# design.net
KiCad netlist of a schematic drawn in Altium Designer
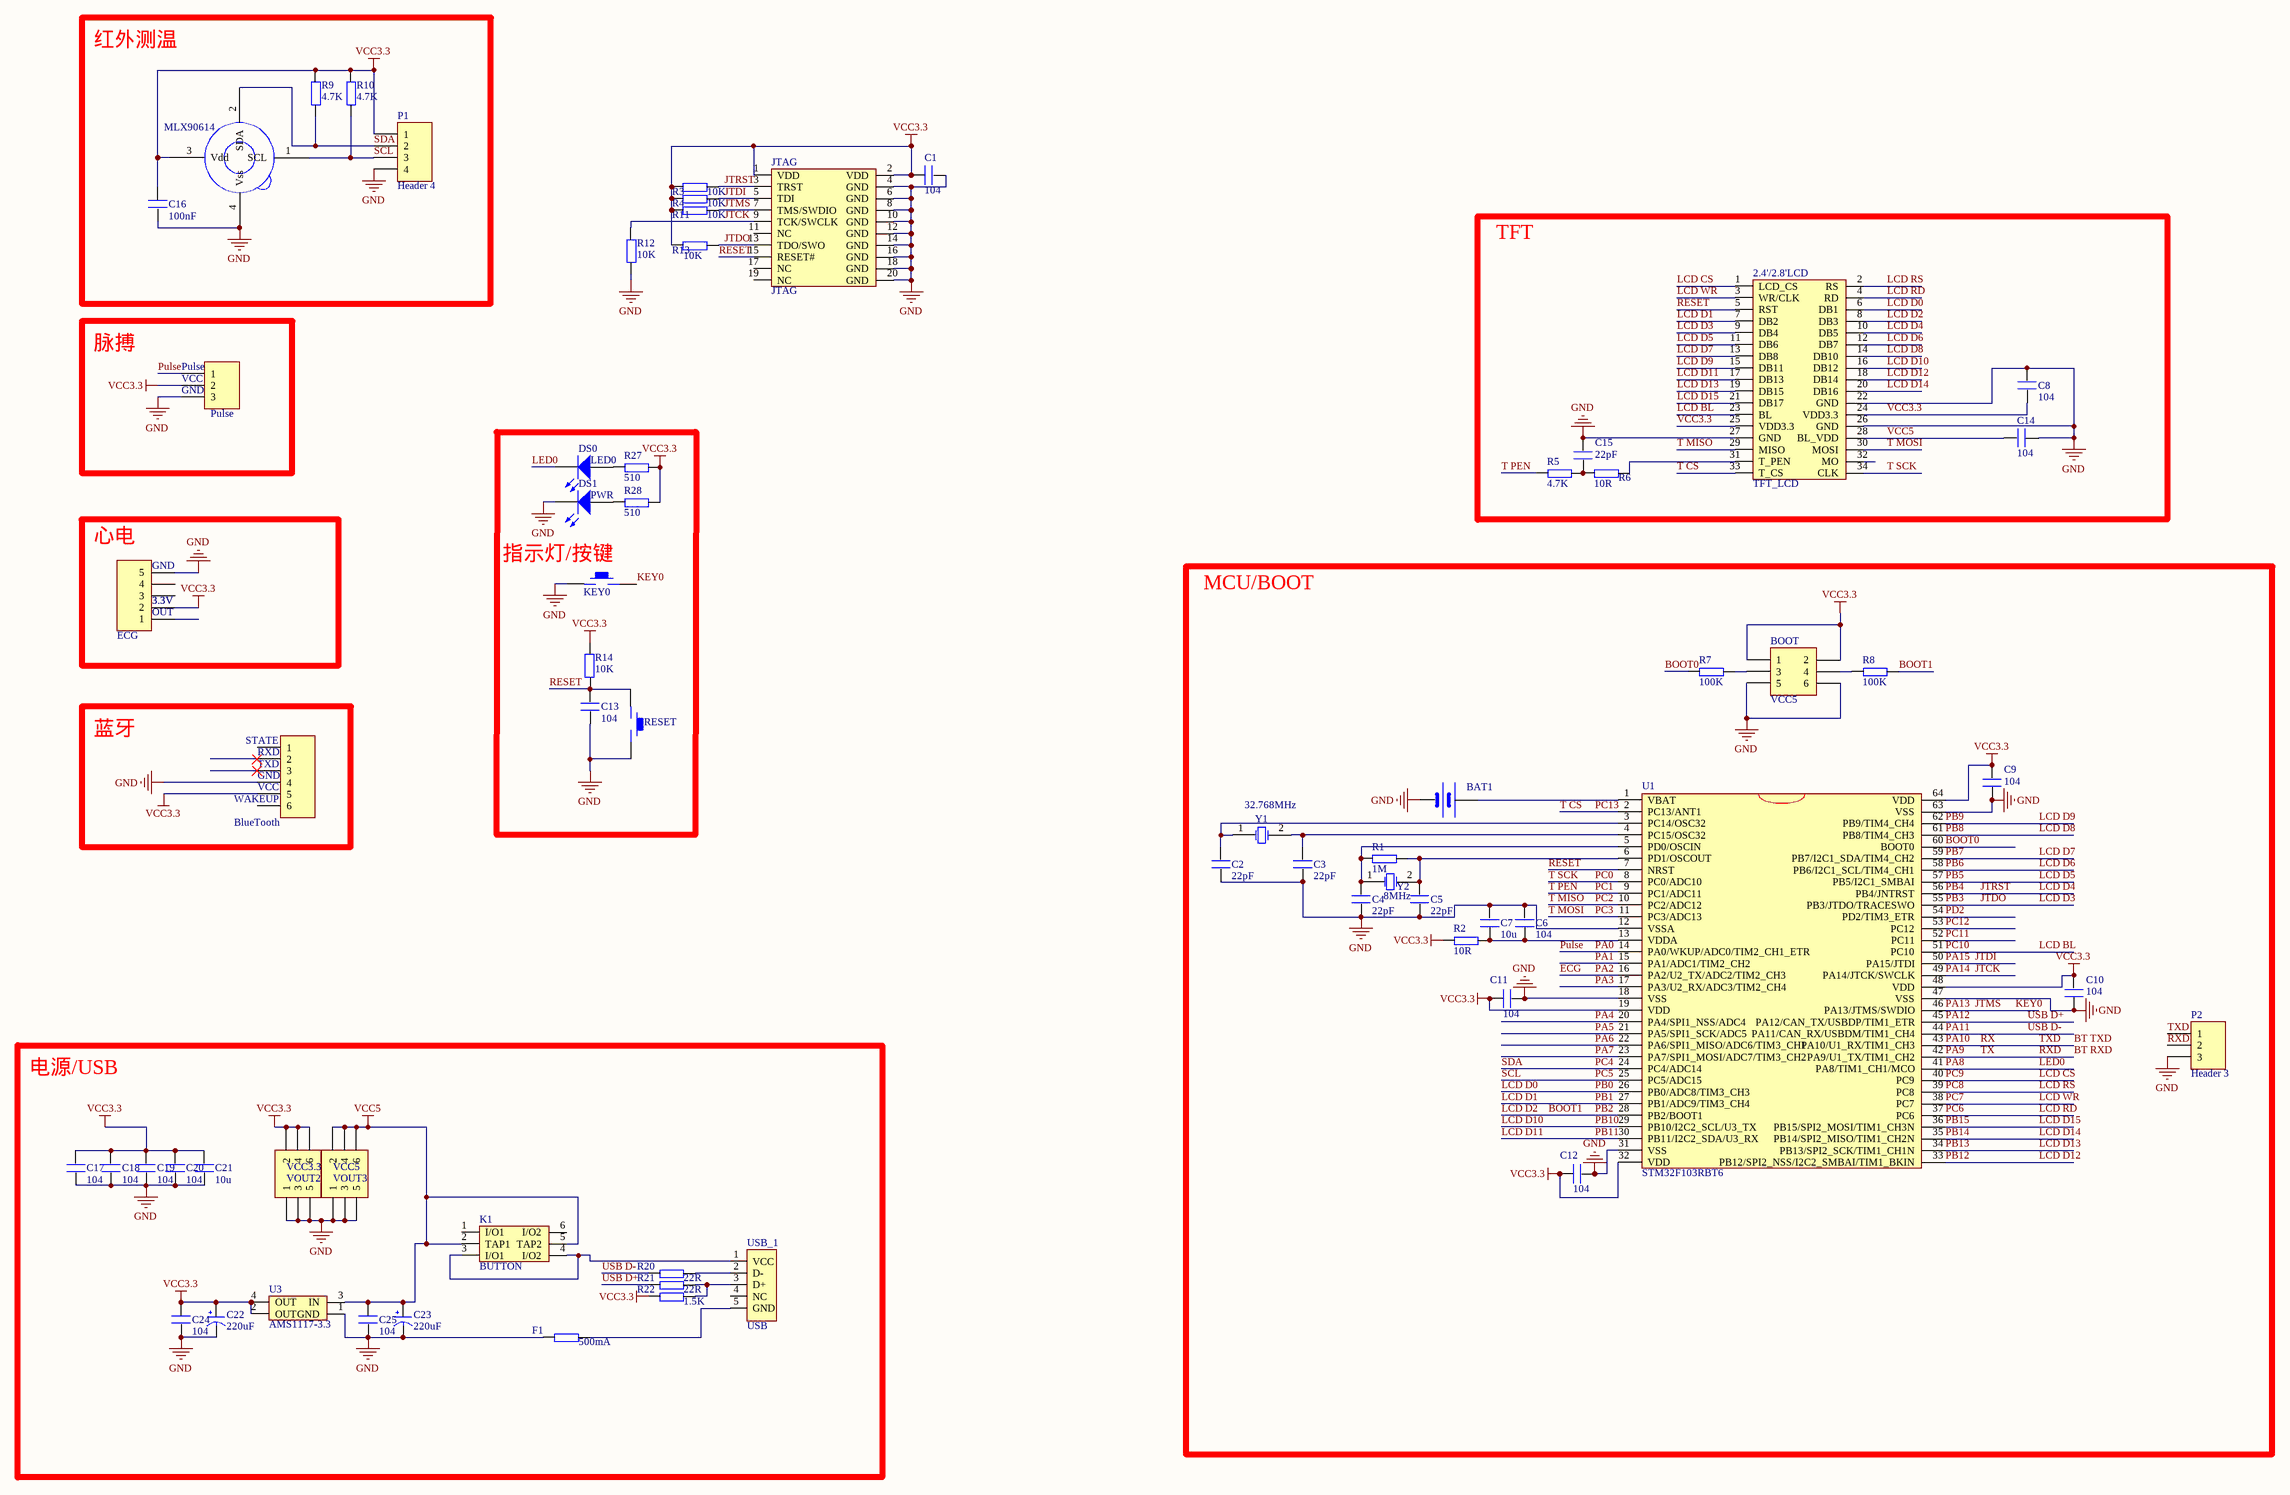
[diagram p0: 远程医疗.SchDoc]

(export (version "E")
  (design (tool "Eeschema 10.0.6"))
  (components
    (comp (ref "2.4'/2.8'LCD")
      (value "TFT_LCD")
      (footprint "DB2*17")
      (libsource (lib "MiniSTM32 V2.0封装库") (part "TFT_LCD"))
    )
    (comp (ref "BAT1") (value "BATT") (footprint "BATM") (libsource (lib "MiniSTM32 V2.0封装库") (part "BAT")))
    (comp (ref "BlueTooth")
      (value "BlueTooth")
      (footprint "BlueTooth")
      (libsource (lib "my Integrated lib ") (part "BlueTooth"))
    )
    (comp (ref "BOOT")
      (value "VCC5")
      (footprint "HDR2X3")
      (description "Header, 3-Pin, Dual row")
      (fields (field (name "PUBLISHER") "Altium Limited"))
      (libsource (lib "MiniSTM32 V2.0封装库") (part "Header 3X2"))
    )
    (comp (ref "C1") (value "104") (footprint "0603P") (libsource (lib "MiniSTM32 V2.0封装库") (part "C")))
    (comp (ref "C2") (value "22pF") (footprint "0603P") (libsource (lib "MiniSTM32 V2.0封装库") (part "C")))
    (comp (ref "C3") (value "22pF") (footprint "0603P") (libsource (lib "MiniSTM32 V2.0封装库") (part "C")))
    (comp (ref "C4") (value "22pF") (footprint "0603P") (libsource (lib "MiniSTM32 V2.0封装库") (part "C")))
    (comp (ref "C5") (value "22pF") (footprint "0603P") (libsource (lib "MiniSTM32 V2.0封装库") (part "C")))
    (comp (ref "C6") (value "104") (footprint "0603P") (libsource (lib "MiniSTM32 V2.0封装库") (part "C")))
    (comp (ref "C7") (value "10u") (footprint "0603P") (libsource (lib "MiniSTM32 V2.0封装库") (part "C")))
    (comp (ref "C8") (value "104") (footprint "0603P") (libsource (lib "MiniSTM32 V2.0封装库") (part "C")))
    (comp (ref "C9") (value "104") (footprint "0603P") (libsource (lib "MiniSTM32 V2.0封装库") (part "C")))
    (comp (ref "C10") (value "104") (footprint "0603P") (libsource (lib "MiniSTM32 V2.0封装库") (part "C")))
    (comp (ref "C11") (value "104") (footprint "0603P") (libsource (lib "MiniSTM32 V2.0封装库") (part "C")))
    (comp (ref "C12") (value "104") (footprint "0603P") (libsource (lib "MiniSTM32 V2.0封装库") (part "C")))
    (comp (ref "C13") (value "104") (footprint "0603P") (libsource (lib "MiniSTM32 V2.0封装库") (part "C")))
    (comp (ref "C14") (value "104") (footprint "0603P") (libsource (lib "MiniSTM32 V2.0封装库") (part "C")))
    (comp (ref "C15") (value "22pF") (footprint "0603P") (libsource (lib "MiniSTM32 V2.0封装库") (part "C")))
    (comp (ref "C16") (value "100nF") (footprint "0603P") (libsource (lib "MiniSTM32 V2.0封装库") (part "C")))
    (comp (ref "C17") (value "104") (footprint "0603P") (libsource (lib "MiniSTM32 V2.0封装库") (part "C")))
    (comp (ref "C18") (value "104") (footprint "0603P") (libsource (lib "MiniSTM32 V2.0封装库") (part "C")))
    (comp (ref "C19") (value "104") (footprint "0603P") (libsource (lib "MiniSTM32 V2.0封装库") (part "C")))
    (comp (ref "C20") (value "104") (footprint "0603P") (libsource (lib "MiniSTM32 V2.0封装库") (part "C")))
    (comp (ref "C21") (value "10u") (footprint "0603P") (libsource (lib "MiniSTM32 V2.0封装库") (part "C")))
    (comp (ref "C22")
      (value "220uF")
      (footprint "CC6.56.5")
      (libsource (lib "MiniSTM32 V2.0封装库") (part "CAP"))
    )
    (comp (ref "C23")
      (value "220uF")
      (footprint "CC6.56.5")
      (libsource (lib "MiniSTM32 V2.0封装库") (part "CAP"))
    )
    (comp (ref "C24") (value "104") (footprint "0603P") (libsource (lib "MiniSTM32 V2.0封装库") (part "C")))
    (comp (ref "C25") (value "104") (footprint "0603P") (libsource (lib "MiniSTM32 V2.0封装库") (part "C")))
    (comp (ref "DS0")
      (value "LED0")
      (footprint "SMDLED")
      (description "Typical RED, GREEN, YELLOW, AMBER GaAs LED")
      (fields (field (name "PUBLISHER") "Altium Limited"))
      (libsource (lib "MiniSTM32 V2.0封装库") (part "LED2"))
    )
    (comp (ref "DS1")
      (value "PWR")
      (footprint "SMDLED")
      (description "Typical RED, GREEN, YELLOW, AMBER GaAs LED")
      (fields (field (name "PUBLISHER") "Altium Limited"))
      (libsource (lib "MiniSTM32 V2.0封装库") (part "LED2"))
    )
    (comp (ref "ECG") (value "ECG") (footprint "ECG") (libsource (lib "my Integrated lib ") (part "ECG")))
    (comp (ref "F1") (value "500mA") (footprint "0603P") (libsource (lib "MiniSTM32 V2.0封装库") (part "R")))
    (comp (ref "JTAG") (value "JTAG") (footprint "JTAG_20") (libsource (lib "CORE") (part "JTAG")))
    (comp (ref "K1")
      (value "BUTTON")
      (footprint "BTN8.5*8.5")
      (libsource (lib "MiniSTM32 V2.0封装库") (part "BUTTON"))
    )
    (comp (ref "KEY0") (value "KEY_M") (footprint "KEY_M") (libsource (lib "") (part "KEY_M_1")))
    (comp (ref "MLX90614")
      (value "MLX90614")
      (footprint "MLX90614")
      (libsource (lib "my Integrated lib ") (part "MLX90614"))
    )
    (comp (ref "P1")
      (value "Header 4")
      (footprint "HDR1X4")
      (description "Header, 4-Pin")
      (fields (field (name "PUBLISHER") "Altium Limited"))
      (libsource (lib "Miscellaneous Connectors") (part "Header 4"))
    )
    (comp (ref "P2")
      (value "Header 3")
      (footprint "HDR1X3")
      (description "Header, 3-Pin")
      (fields (field (name "PUBLISHER") "Altium Limited"))
      (libsource (lib "Miscellaneous Connectors") (part "Header 3"))
    )
    (comp (ref "Pulse")
      (value "Pulse")
      (footprint "Pulse")
      (libsource (lib "my Integrated lib ") (part "Pulse"))
    )
    (comp (ref "R1") (value "1M") (footprint "0603P") (libsource (lib "MiniSTM32 V2.0封装库") (part "R")))
    (comp (ref "R2") (value "10R") (footprint "0603P") (libsource (lib "MiniSTM32 V2.0封装库") (part "R")))
    (comp (ref "R3") (value "10K") (footprint "0603P") (libsource (lib "MiniSTM32 V2.0封装库") (part "R")))
    (comp (ref "R4") (value "10K") (footprint "0603P") (libsource (lib "MiniSTM32 V2.0封装库") (part "R")))
    (comp (ref "R5") (value "4.7K") (footprint "0603P") (libsource (lib "MiniSTM32 V2.0封装库") (part "R")))
    (comp (ref "R6") (value "10R") (footprint "0603P") (libsource (lib "MiniSTM32 V2.0封装库") (part "R")))
    (comp (ref "R7") (value "100K") (footprint "0603P") (libsource (lib "MiniSTM32 V2.0封装库") (part "R")))
    (comp (ref "R8") (value "100K") (footprint "0603P") (libsource (lib "MiniSTM32 V2.0封装库") (part "R")))
    (comp (ref "R9") (value "4.7K") (footprint "0603P") (libsource (lib "MiniSTM32 V2.0封装库") (part "R")))
    (comp (ref "R10") (value "4.7K") (footprint "0603P") (libsource (lib "MiniSTM32 V2.0封装库") (part "R")))
    (comp (ref "R11") (value "10K") (footprint "0603P") (libsource (lib "MiniSTM32 V2.0封装库") (part "R")))
    (comp (ref "R12") (value "10K") (footprint "0603P") (libsource (lib "MiniSTM32 V2.0封装库") (part "R")))
    (comp (ref "R13") (value "10K") (footprint "0603P") (libsource (lib "MiniSTM32 V2.0封装库") (part "R")))
    (comp (ref "R14") (value "10K") (footprint "0603P") (libsource (lib "MiniSTM32 V2.0封装库") (part "R")))
    (comp (ref "R20") (value "22R") (footprint "0603P") (libsource (lib "MiniSTM32 V2.0封装库") (part "R")))
    (comp (ref "R21") (value "22R") (footprint "0603P") (libsource (lib "MiniSTM32 V2.0封装库") (part "R")))
    (comp (ref "R22") (value "1.5K") (footprint "0603P") (libsource (lib "MiniSTM32 V2.0封装库") (part "R")))
    (comp (ref "R27") (value "510") (footprint "0603P") (libsource (lib "MiniSTM32 V2.0封装库") (part "R")))
    (comp (ref "R28") (value "510") (footprint "0603P") (libsource (lib "MiniSTM32 V2.0封装库") (part "R")))
    (comp (ref "RESET")
      (value "KEY_M")
      (footprint "KEY_M")
      (libsource (lib "MiniSTM32 V2.0封装库") (part "KEY_M"))
    )
    (comp (ref "U1")
      (value "STM32F103RBT6")
      (footprint "STM32F103RXT")
      (libsource (lib "MiniSTM32 V2.0封装库") (part "STM32F103RBT6"))
    )
    (comp (ref "U3")
      (value "AMS1117-3.3")
      (footprint "AMS1117")
      (libsource (lib "MiniSTM32 V2.0封装库") (part "AMS1117"))
    )
    (comp (ref "USB_1")
      (value "USB")
      (footprint "USB/SM0.8-6H5")
      (libsource (lib "MiniSTM32 V2.0封装库") (part "USB5"))
    )
    (comp (ref "VOUT2")
      (value "VCC3.3")
      (footprint "HDR2X3")
      (description "Header, 3-Pin, Dual row")
      (fields (field (name "PUBLISHER") "Altium Limited"))
      (libsource (lib "") (part "Header 3X2_1"))
    )
    (comp (ref "VOUT3")
      (value "VCC5")
      (footprint "HDR2X3")
      (description "Header, 3-Pin, Dual row")
      (fields (field (name "PUBLISHER") "Altium Limited"))
      (libsource (lib "") (part "Header 3X2_1"))
    )
    (comp (ref "Y1")
      (value "32.768MHz")
      (footprint "XTAL 32M")
      (description "Crystal Oscillator")
      (fields (field (name "PUBLISHER") "Altium Limited"))
      (libsource (lib "MiniSTM32 V2.0封装库") (part "XTAL"))
    )
    (comp (ref "Y2")
      (value "8MHz")
      (footprint "XTAL_US")
      (description "Crystal Oscillator")
      (fields (field (name "PUBLISHER") "Altium Limited"))
      (libsource (lib "MiniSTM32 V2.0封装库") (part "XTAL"))
    )
  )
  (nets
    (net (code "1") (name "/BOOT0") (class "Default")
      (node (ref "R7") (pin "1") (pintype "passive"))
      (node (ref "U1") (pin "60") (pinfunction "BOOT0_60") (pintype "passive"))
    )
    (net (code "2") (name "/BOOT1") (class "Default")
      (node (ref "2.4'/2.8'LCD") (pin "8") (pinfunction "DB3_8") (pintype "passive"))
      (node (ref "R8") (pin "2") (pintype "passive"))
      (node (ref "U1") (pin "28") (pinfunction "PB2/BOOT1_28") (pintype "passive"))
    )
    (net (code "3") (name "/BT RXD") (class "Default")
      (node (ref "P2") (pin "2") (pinfunction "2_2") (pintype "passive"))
      (node (ref "U1") (pin "42") (pinfunction "PA9/U1_TX/TIM1_CH2_42") (pintype "passive"))
    )
    (net (code "4") (name "/BT TXD") (class "Default")
      (node (ref "P2") (pin "1") (pinfunction "1_1") (pintype "passive"))
      (node (ref "U1") (pin "43") (pinfunction "PA10/U1_RX/TIM1_CH3_43") (pintype "passive"))
    )
    (net (code "5") (name "/ECG") (class "Default")
      (node (ref "U1") (pin "16") (pinfunction "PA2/U2_TX/ADC2/TIM2_CH3_16") (pintype "passive"))
    )
    (net (code "6") (name "/JTCK") (class "Default")
      (node (ref "JTAG") (pin "9") (pinfunction "TCK/SWCLK_9") (pintype "passive"))
      (node (ref "R12") (pin "2") (pintype "passive"))
      (node (ref "U1") (pin "49") (pinfunction "PA14/JTCK/SWCLK_49") (pintype "passive"))
    )
    (net (code "7") (name "/JTDI") (class "Default")
      (node (ref "JTAG") (pin "5") (pinfunction "TDI_5") (pintype "passive"))
      (node (ref "R4") (pin "2") (pintype "passive"))
      (node (ref "U1") (pin "50") (pinfunction "PA15/JTDI_50") (pintype "passive"))
    )
    (net (code "8") (name "/JTDO") (class "Default")
      (node (ref "2.4'/2.8'LCD") (pin "9") (pinfunction "DB4_9") (pintype "passive"))
      (node (ref "JTAG") (pin "13") (pinfunction "TDO/SWO_13") (pintype "passive"))
      (node (ref "R13") (pin "2") (pintype "passive"))
      (node (ref "U1") (pin "55") (pinfunction "PB3/JTDO/TRACESWO_55") (pintype "passive"))
    )
    (net (code "9") (name "/JTMS") (class "Default")
      (node (ref "JTAG") (pin "7") (pinfunction "TMS/SWDIO_7") (pintype "passive"))
      (node (ref "KEY0") (pin "2") (pinfunction "2_2") (pintype "passive"))
      (node (ref "R11") (pin "2") (pintype "passive"))
      (node (ref "U1") (pin "46") (pinfunction "PA13/JTMS/SWDIO_46") (pintype "passive"))
    )
    (net (code "10") (name "/JTRST") (class "Default")
      (node (ref "2.4'/2.8'LCD") (pin "10") (pinfunction "DB5_10") (pintype "passive"))
      (node (ref "JTAG") (pin "3") (pinfunction "TRST_3") (pintype "passive"))
      (node (ref "R3") (pin "2") (pintype "passive"))
      (node (ref "U1") (pin "56") (pinfunction "PB4/JNTRST_56") (pintype "passive"))
    )
    (net (code "11") (name "/LCD BL") (class "Default")
      (node (ref "2.4'/2.8'LCD") (pin "23") (pinfunction "BL_23") (pintype "passive"))
      (node (ref "U1") (pin "51") (pinfunction "PC10_51") (pintype "passive"))
    )
    (net (code "12") (name "/LCD CS") (class "Default")
      (node (ref "2.4'/2.8'LCD") (pin "1") (pinfunction "LCD_CS_1") (pintype "passive"))
      (node (ref "U1") (pin "40") (pinfunction "PC9_40") (pintype "passive"))
    )
    (net (code "13") (name "/LCD D0") (class "Default")
      (node (ref "2.4'/2.8'LCD") (pin "6") (pinfunction "DB1_6") (pintype "passive"))
      (node (ref "U1") (pin "26") (pinfunction "PB0/ADC8/TIM3_CH3_26") (pintype "passive"))
    )
    (net (code "14") (name "/LCD D1") (class "Default")
      (node (ref "2.4'/2.8'LCD") (pin "7") (pinfunction "DB2_7") (pintype "passive"))
      (node (ref "U1") (pin "27") (pinfunction "PB1/ADC9/TIM3_CH4_27") (pintype "passive"))
    )
    (net (code "15") (name "/LCD D5") (class "Default")
      (node (ref "2.4'/2.8'LCD") (pin "11") (pinfunction "DB6_11") (pintype "passive"))
      (node (ref "U1") (pin "57") (pinfunction "PB5/I2C1_SMBAI_57") (pintype "passive"))
    )
    (net (code "16") (name "/LCD D6") (class "Default")
      (node (ref "2.4'/2.8'LCD") (pin "12") (pinfunction "DB7_12") (pintype "passive"))
      (node (ref "U1") (pin "58") (pinfunction "PB6/I2C1_SCL/TIM4_CH1_58") (pintype "passive"))
    )
    (net (code "17") (name "/LCD D7") (class "Default")
      (node (ref "2.4'/2.8'LCD") (pin "13") (pinfunction "DB8_13") (pintype "passive"))
      (node (ref "U1") (pin "59") (pinfunction "PB7/I2C1_SDA/TIM4_CH2_59") (pintype "passive"))
    )
    (net (code "18") (name "/LCD D8") (class "Default")
      (node (ref "2.4'/2.8'LCD") (pin "14") (pinfunction "DB10_14") (pintype "passive"))
      (node (ref "U1") (pin "61") (pinfunction "PB8/TIM4_CH3_61") (pintype "passive"))
    )
    (net (code "19") (name "/LCD D9") (class "Default")
      (node (ref "2.4'/2.8'LCD") (pin "15") (pinfunction "DB11_15") (pintype "passive"))
      (node (ref "U1") (pin "62") (pinfunction "PB9/TIM4_CH4_62") (pintype "passive"))
    )
    (net (code "20") (name "/LCD D10") (class "Default")
      (node (ref "2.4'/2.8'LCD") (pin "16") (pinfunction "DB12_16") (pintype "passive"))
      (node (ref "U1") (pin "29") (pinfunction "PB10/I2C2_SCL/U3_TX_29") (pintype "passive"))
    )
    (net (code "21") (name "/LCD D11") (class "Default")
      (node (ref "2.4'/2.8'LCD") (pin "17") (pinfunction "DB13_17") (pintype "passive"))
      (node (ref "U1") (pin "30") (pinfunction "PB11/I2C2_SDA/U3_RX_30") (pintype "passive"))
    )
    (net (code "22") (name "/LCD D12") (class "Default")
      (node (ref "2.4'/2.8'LCD") (pin "18") (pinfunction "DB14_18") (pintype "passive"))
      (node (ref "U1") (pin "33") (pinfunction "PB12/SPI2_NSS/I2C2_SMBAI/TIM1_BKIN_33") (pintype "passive"))
    )
    (net (code "23") (name "/LCD D13") (class "Default")
      (node (ref "2.4'/2.8'LCD") (pin "19") (pinfunction "DB15_19") (pintype "passive"))
      (node (ref "U1") (pin "34") (pinfunction "PB13/SPI2_SCK/TIM1_CH1N_34") (pintype "passive"))
    )
    (net (code "24") (name "/LCD D14") (class "Default")
      (node (ref "2.4'/2.8'LCD") (pin "20") (pinfunction "DB16_20") (pintype "passive"))
      (node (ref "U1") (pin "35") (pinfunction "PB14/SPI2_MISO/TIM1_CH2N_35") (pintype "passive"))
    )
    (net (code "25") (name "/LCD D15") (class "Default")
      (node (ref "2.4'/2.8'LCD") (pin "21") (pinfunction "DB17_21") (pintype "passive"))
      (node (ref "U1") (pin "36") (pinfunction "PB15/SPI2_MOSI/TIM1_CH3N_36") (pintype "passive"))
    )
    (net (code "26") (name "/LCD RD") (class "Default")
      (node (ref "2.4'/2.8'LCD") (pin "4") (pinfunction "RD_4") (pintype "passive"))
      (node (ref "U1") (pin "37") (pinfunction "PC6_37") (pintype "passive"))
    )
    (net (code "27") (name "/LCD RS") (class "Default")
      (node (ref "2.4'/2.8'LCD") (pin "2") (pinfunction "RS_2") (pintype "passive"))
      (node (ref "U1") (pin "39") (pinfunction "PC8_39") (pintype "passive"))
    )
    (net (code "28") (name "/LCD WR") (class "Default")
      (node (ref "2.4'/2.8'LCD") (pin "3") (pinfunction "WR/CLK_3") (pintype "passive"))
      (node (ref "U1") (pin "38") (pinfunction "PC7_38") (pintype "passive"))
    )
    (net (code "29") (name "/LED0") (class "Default")
      (node (ref "DS0") (pin "2") (pinfunction "K_2") (pintype "passive"))
      (node (ref "U1") (pin "41") (pinfunction "PA8/TIM1_CH1/MCO_41") (pintype "passive"))
    )
    (net (code "30") (name "/PA0") (class "Default")
      (node (ref "Pulse") (pin "1") (pinfunction "1_1") (pintype "passive"))
      (node (ref "U1") (pin "14") (pinfunction "PA0/WKUP/ADC0/TIM2_CH1_ETR_14") (pintype "passive"))
    )
    (net (code "31") (name "/PA1") (class "Default")
      (node (ref "U1") (pin "15") (pinfunction "PA1/ADC1/TIM2_CH2_15") (pintype "passive"))
    )
    (net (code "32") (name "/PA3") (class "Default")
      (node (ref "U1") (pin "17") (pinfunction "PA3/U2_RX/ADC3/TIM2_CH4_17") (pintype "passive"))
    )
    (net (code "33") (name "/PA4") (class "Default")
      (node (ref "U1") (pin "20") (pinfunction "PA4/SPI1_NSS/ADC4_20") (pintype "passive"))
    )
    (net (code "34") (name "/PA5") (class "Default")
      (node (ref "U1") (pin "21") (pinfunction "PA5/SPI1_SCK/ADC5_21") (pintype "passive"))
    )
    (net (code "35") (name "/PA6") (class "Default")
      (node (ref "U1") (pin "22") (pinfunction "PA6/SPI1_MISO/ADC6/TIM3_CH1_22") (pintype "passive"))
    )
    (net (code "36") (name "/PA7") (class "Default")
      (node (ref "U1") (pin "23") (pinfunction "PA7/SPI1_MOSI/ADC7/TIM3_CH2_23") (pintype "passive"))
    )
    (net (code "37") (name "/PA11") (class "Default")
      (node (ref "R20") (pin "1") (pintype "passive"))
      (node (ref "U1") (pin "44") (pinfunction "PA11/CAN_RX/USBDM/TIM1_CH4_44") (pintype "passive"))
    )
    (net (code "38") (name "/PA12") (class "Default")
      (node (ref "R21") (pin "1") (pintype "passive"))
      (node (ref "U1") (pin "45") (pinfunction "PA12/CAN_TX/USBDP/TIM1_ETR_45") (pintype "passive"))
    )
    (net (code "39") (name "/PC0") (class "Default")
      (node (ref "2.4'/2.8'LCD") (pin "34") (pinfunction "CLK_34") (pintype "passive"))
      (node (ref "U1") (pin "8") (pinfunction "PC0/ADC10_8") (pintype "passive"))
    )
    (net (code "40") (name "/PC1") (class "Default")
      (node (ref "R5") (pin "1") (pintype "passive"))
      (node (ref "U1") (pin "9") (pinfunction "PC1/ADC11_9") (pintype "passive"))
    )
    (net (code "41") (name "/PC2") (class "Default")
      (node (ref "2.4'/2.8'LCD") (pin "29") (pinfunction "MISO_29") (pintype "passive"))
      (node (ref "U1") (pin "10") (pinfunction "PC2/ADC12_10") (pintype "passive"))
    )
    (net (code "42") (name "/PC3") (class "Default")
      (node (ref "2.4'/2.8'LCD") (pin "30") (pinfunction "MOSI_30") (pintype "passive"))
      (node (ref "U1") (pin "11") (pinfunction "PC3/ADC13_11") (pintype "passive"))
    )
    (net (code "43") (name "/PC4") (class "Default")
      (node (ref "MLX90614") (pin "2") (pinfunction "SDA_2") (pintype "passive"))
      (node (ref "P1") (pin "2") (pinfunction "2_2") (pintype "passive"))
      (node (ref "R9") (pin "1") (pintype "passive"))
      (node (ref "U1") (pin "24") (pinfunction "PC4/ADC14_24") (pintype "passive"))
    )
    (net (code "44") (name "/PC5") (class "Default")
      (node (ref "MLX90614") (pin "1") (pinfunction "SCL_1") (pintype "passive"))
      (node (ref "P1") (pin "3") (pinfunction "3_3") (pintype "passive"))
      (node (ref "R10") (pin "1") (pintype "passive"))
      (node (ref "U1") (pin "25") (pinfunction "PC5/ADC15_25") (pintype "passive"))
    )
    (net (code "45") (name "/PC11") (class "Default")
      (node (ref "U1") (pin "52") (pinfunction "PC11_52") (pintype "passive"))
    )
    (net (code "46") (name "/PC12") (class "Default")
      (node (ref "U1") (pin "53") (pinfunction "PC12_53") (pintype "passive"))
    )
    (net (code "47") (name "/PC13") (class "Default")
      (node (ref "2.4'/2.8'LCD") (pin "33") (pinfunction "T_CS_33") (pintype "passive"))
      (node (ref "U1") (pin "2") (pinfunction "PC13/ANT1_2") (pintype "passive"))
    )
    (net (code "48") (name "/PD2") (class "Default")
      (node (ref "U1") (pin "54") (pinfunction "PD2/TIM3_ETR_54") (pintype "passive"))
    )
    (net (code "49") (name "/RESET") (class "Default")
      (node (ref "2.4'/2.8'LCD") (pin "5") (pinfunction "RST_5") (pintype "passive"))
      (node (ref "C13") (pin "1") (pintype "passive"))
      (node (ref "JTAG") (pin "15") (pinfunction "RESET#_15") (pintype "passive"))
      (node (ref "R14") (pin "2") (pintype "passive"))
      (node (ref "RESET") (pin "1") (pinfunction "1_1") (pintype "passive"))
      (node (ref "U1") (pin "7") (pinfunction "NRST_7") (pintype "passive"))
    )
    (net (code "50") (name "GND") (class "Default")
      (node (ref "2.4'/2.8'LCD") (pin "22") (pinfunction "GND_22") (pintype "passive"))
      (node (ref "2.4'/2.8'LCD") (pin "26") (pinfunction "GND_26") (pintype "passive"))
      (node (ref "2.4'/2.8'LCD") (pin "27") (pinfunction "GND_27") (pintype "passive"))
      (node (ref "BAT1") (pin "2") (pinfunction "GND_2") (pintype "passive"))
      (node (ref "BOOT") (pin "5") (pinfunction "5_5") (pintype "passive"))
      (node (ref "BOOT") (pin "6") (pinfunction "6_6") (pintype "passive"))
      (node (ref "BlueTooth") (pin "4") (pinfunction "4_4") (pintype "passive"))
      (node (ref "C1") (pin "2") (pintype "passive"))
      (node (ref "C10") (pin "2") (pintype "passive"))
      (node (ref "C11") (pin "2") (pintype "passive"))
      (node (ref "C12") (pin "2") (pintype "passive"))
      (node (ref "C13") (pin "2") (pintype "passive"))
      (node (ref "C14") (pin "1") (pintype "passive"))
      (node (ref "C15") (pin "2") (pintype "passive"))
      (node (ref "C16") (pin "1") (pintype "passive"))
      (node (ref "C17") (pin "2") (pintype "passive"))
      (node (ref "C18") (pin "2") (pintype "passive"))
      (node (ref "C19") (pin "2") (pintype "passive"))
      (node (ref "C2") (pin "1") (pintype "passive"))
      (node (ref "C20") (pin "2") (pintype "passive"))
      (node (ref "C21") (pin "2") (pintype "passive"))
      (node (ref "C22") (pin "2") (pinfunction "GND_2") (pintype "passive"))
      (node (ref "C23") (pin "2") (pinfunction "GND_2") (pintype "passive"))
      (node (ref "C24") (pin "1") (pintype "passive"))
      (node (ref "C25") (pin "1") (pintype "passive"))
      (node (ref "C3") (pin "1") (pintype "passive"))
      (node (ref "C4") (pin "1") (pintype "passive"))
      (node (ref "C5") (pin "1") (pintype "passive"))
      (node (ref "C6") (pin "1") (pintype "passive"))
      (node (ref "C7") (pin "1") (pintype "passive"))
      (node (ref "C8") (pin "2") (pintype "passive"))
      (node (ref "C9") (pin "2") (pintype "passive"))
      (node (ref "DS1") (pin "2") (pinfunction "K_2") (pintype "passive"))
      (node (ref "ECG") (pin "5") (pinfunction "5_5") (pintype "passive"))
      (node (ref "F1") (pin "1") (pintype "passive"))
      (node (ref "JTAG") (pin "10") (pinfunction "GND_10") (pintype "passive"))
      (node (ref "JTAG") (pin "12") (pinfunction "GND_12") (pintype "passive"))
      (node (ref "JTAG") (pin "14") (pinfunction "GND_14") (pintype "passive"))
      (node (ref "JTAG") (pin "16") (pinfunction "GND_16") (pintype "passive"))
      (node (ref "JTAG") (pin "18") (pinfunction "GND_18") (pintype "passive"))
      (node (ref "JTAG") (pin "20") (pinfunction "GND_20") (pintype "passive"))
      (node (ref "JTAG") (pin "4") (pinfunction "GND_4") (pintype "passive"))
      (node (ref "JTAG") (pin "6") (pinfunction "GND_6") (pintype "passive"))
      (node (ref "JTAG") (pin "8") (pinfunction "GND_8") (pintype "passive"))
      (node (ref "KEY0") (pin "1") (pinfunction "1_1") (pintype "passive"))
      (node (ref "MLX90614") (pin "4") (pinfunction "Vss_4") (pintype "passive"))
      (node (ref "P1") (pin "4") (pinfunction "4_4") (pintype "passive"))
      (node (ref "P2") (pin "3") (pinfunction "3_3") (pintype "passive"))
      (node (ref "Pulse") (pin "3") (pinfunction "3_3") (pintype "passive"))
      (node (ref "R12") (pin "1") (pintype "passive"))
      (node (ref "RESET") (pin "2") (pinfunction "2_2") (pintype "passive"))
      (node (ref "U1") (pin "12") (pinfunction "VSSA_12") (pintype "passive"))
      (node (ref "U1") (pin "18") (pinfunction "VSS_18") (pintype "passive"))
      (node (ref "U1") (pin "31") (pinfunction "VSS_31") (pintype "passive"))
      (node (ref "U1") (pin "47") (pinfunction "VSS_47") (pintype "passive"))
      (node (ref "U1") (pin "63") (pinfunction "VSS_63") (pintype "passive"))
      (node (ref "U3") (pin "1") (pinfunction "GND_1") (pintype "passive"))
      (node (ref "VOUT2") (pin "1") (pinfunction "1_1") (pintype "passive"))
      (node (ref "VOUT2") (pin "3") (pinfunction "3_3") (pintype "passive"))
      (node (ref "VOUT2") (pin "5") (pinfunction "5_5") (pintype "passive"))
      (node (ref "VOUT3") (pin "1") (pinfunction "1_1") (pintype "passive"))
      (node (ref "VOUT3") (pin "3") (pinfunction "3_3") (pintype "passive"))
      (node (ref "VOUT3") (pin "5") (pinfunction "5_5") (pintype "passive"))
    )
    (net (code "51") (name "Net-(2.4'/2.8'LCD-T_PEN)") (class "Default")
      (node (ref "2.4'/2.8'LCD") (pin "31") (pinfunction "T_PEN_31") (pintype "passive"))
      (node (ref "R6") (pin "2") (pintype "passive"))
    )
    (net (code "52") (name "Net-(BAT1-VCC)") (class "Default")
      (node (ref "BAT1") (pin "1") (pinfunction "VCC_1") (pintype "passive"))
      (node (ref "U1") (pin "1") (pinfunction "VBAT_1") (pintype "passive"))
    )
    (net (code "53") (name "Net-(BOOT-Pad3)") (class "Default")
      (node (ref "BOOT") (pin "3") (pinfunction "3_3") (pintype "passive"))
      (node (ref "R7") (pin "2") (pintype "passive"))
    )
    (net (code "54") (name "Net-(BOOT-Pad4)") (class "Default")
      (node (ref "BOOT") (pin "4") (pinfunction "4_4") (pintype "passive"))
      (node (ref "R8") (pin "1") (pintype "passive"))
    )
    (net (code "55") (name "Net-(C15-Pad1)") (class "Default")
      (node (ref "C15") (pin "1") (pintype "passive"))
      (node (ref "R5") (pin "2") (pintype "passive"))
      (node (ref "R6") (pin "1") (pintype "passive"))
    )
    (net (code "56") (name "Net-(DS0-A)") (class "Default")
      (node (ref "DS0") (pin "1") (pinfunction "A_1") (pintype "passive"))
      (node (ref "R27") (pin "1") (pintype "passive"))
    )
    (net (code "57") (name "Net-(DS1-A)") (class "Default")
      (node (ref "DS1") (pin "1") (pinfunction "A_1") (pintype "passive"))
      (node (ref "R28") (pin "1") (pintype "passive"))
    )
    (net (code "58") (name "Net-(U1-PC14{slash}OSC32)") (class "Default")
      (node (ref "C2") (pin "2") (pintype "passive"))
      (node (ref "U1") (pin "3") (pinfunction "PC14/OSC32_3") (pintype "passive"))
      (node (ref "Y1") (pin "1") (pinfunction "OSC1_1") (pintype "passive"))
    )
    (net (code "59") (name "Net-(U1-PC15{slash}OSC32)") (class "Default")
      (node (ref "C3") (pin "2") (pintype "passive"))
      (node (ref "U1") (pin "4") (pinfunction "PC15/OSC32_4") (pintype "passive"))
      (node (ref "Y1") (pin "2") (pinfunction "OSC2_2") (pintype "passive"))
    )
    (net (code "60") (name "Net-(U1-PD0{slash}OSCIN)") (class "Default")
      (node (ref "C4") (pin "2") (pintype "passive"))
      (node (ref "R1") (pin "1") (pintype "passive"))
      (node (ref "U1") (pin "5") (pinfunction "PD0/OSCIN_5") (pintype "passive"))
      (node (ref "Y2") (pin "1") (pinfunction "OSC1_1") (pintype "passive"))
    )
    (net (code "61") (name "Net-(U1-PD1{slash}OSCOUT)") (class "Default")
      (node (ref "C5") (pin "2") (pintype "passive"))
      (node (ref "R1") (pin "2") (pintype "passive"))
      (node (ref "U1") (pin "6") (pinfunction "PD1/OSCOUT_6") (pintype "passive"))
      (node (ref "Y2") (pin "2") (pinfunction "OSC2_2") (pintype "passive"))
    )
    (net (code "62") (name "Net-(U1-VDDA)") (class "Default")
      (node (ref "C6") (pin "2") (pintype "passive"))
      (node (ref "C7") (pin "2") (pintype "passive"))
      (node (ref "R2") (pin "2") (pintype "passive"))
      (node (ref "U1") (pin "13") (pinfunction "VDDA_13") (pintype "passive"))
    )
    (net (code "63") (name "Net-(USB_1-D+)") (class "Default")
      (node (ref "R21") (pin "2") (pintype "passive"))
      (node (ref "R22") (pin "2") (pintype "passive"))
      (node (ref "USB_1") (pin "3") (pinfunction "D+_3") (pintype "passive"))
    )
    (net (code "64") (name "Net-(USB_1-D-)") (class "Default")
      (node (ref "R20") (pin "2") (pintype "passive"))
      (node (ref "USB_1") (pin "2") (pinfunction "D-_2") (pintype "passive"))
    )
    (net (code "65") (name "Net-(USB_1-GND)") (class "Default")
      (node (ref "F1") (pin "2") (pintype "passive"))
      (node (ref "USB_1") (pin "5") (pinfunction "GND_5") (pintype "passive"))
    )
    (net (code "66") (name "Net-(USB_1-VCC)") (class "Default")
      (node (ref "K1") (pin "3") (pinfunction "I/O1_3") (pintype "passive"))
      (node (ref "K1") (pin "4") (pinfunction "I/O2_4") (pintype "passive"))
      (node (ref "USB_1") (pin "1") (pinfunction "VCC_1") (pintype "passive"))
    )
    (net (code "67") (name "VCC3.3") (class "Default")
      (node (ref "2.4'/2.8'LCD") (pin "24") (pinfunction "VDD3.3_24") (pintype "passive"))
      (node (ref "2.4'/2.8'LCD") (pin "25") (pinfunction "VDD3.3_25") (pintype "passive"))
      (node (ref "BOOT") (pin "1") (pinfunction "1_1") (pintype "passive"))
      (node (ref "BOOT") (pin "2") (pinfunction "2_2") (pintype "passive"))
      (node (ref "BlueTooth") (pin "5") (pinfunction "5_5") (pintype "passive"))
      (node (ref "C1") (pin "1") (pintype "passive"))
      (node (ref "C10") (pin "1") (pintype "passive"))
      (node (ref "C11") (pin "1") (pintype "passive"))
      (node (ref "C12") (pin "1") (pintype "passive"))
      (node (ref "C16") (pin "2") (pintype "passive"))
      (node (ref "C17") (pin "1") (pintype "passive"))
      (node (ref "C18") (pin "1") (pintype "passive"))
      (node (ref "C19") (pin "1") (pintype "passive"))
      (node (ref "C20") (pin "1") (pintype "passive"))
      (node (ref "C21") (pin "1") (pintype "passive"))
      (node (ref "C22") (pin "1") (pinfunction "VCC_1") (pintype "passive"))
      (node (ref "C24") (pin "2") (pintype "passive"))
      (node (ref "C8") (pin "1") (pintype "passive"))
      (node (ref "C9") (pin "1") (pintype "passive"))
      (node (ref "ECG") (pin "2") (pinfunction "2_2") (pintype "passive"))
      (node (ref "JTAG") (pin "1") (pinfunction "VDD_1") (pintype "passive"))
      (node (ref "JTAG") (pin "2") (pinfunction "VDD_2") (pintype "passive"))
      (node (ref "MLX90614") (pin "3") (pinfunction "Vdd_3") (pintype "passive"))
      (node (ref "P1") (pin "1") (pinfunction "1_1") (pintype "passive"))
      (node (ref "Pulse") (pin "2") (pinfunction "2_2") (pintype "passive"))
      (node (ref "R10") (pin "2") (pintype "passive"))
      (node (ref "R11") (pin "1") (pintype "passive"))
      (node (ref "R13") (pin "1") (pintype "passive"))
      (node (ref "R14") (pin "1") (pintype "passive"))
      (node (ref "R2") (pin "1") (pintype "passive"))
      (node (ref "R22") (pin "1") (pintype "passive"))
      (node (ref "R27") (pin "2") (pintype "passive"))
      (node (ref "R28") (pin "2") (pintype "passive"))
      (node (ref "R3") (pin "1") (pintype "passive"))
      (node (ref "R4") (pin "1") (pintype "passive"))
      (node (ref "R9") (pin "2") (pintype "passive"))
      (node (ref "U1") (pin "19") (pinfunction "VDD_19") (pintype "passive"))
      (node (ref "U1") (pin "32") (pinfunction "VDD_32") (pintype "passive"))
      (node (ref "U1") (pin "48") (pinfunction "VDD_48") (pintype "passive"))
      (node (ref "U1") (pin "64") (pinfunction "VDD_64") (pintype "passive"))
      (node (ref "U3") (pin "2") (pinfunction "OUT_2") (pintype "passive"))
      (node (ref "U3") (pin "4") (pinfunction "OUT_4") (pintype "passive"))
      (node (ref "VOUT2") (pin "2") (pinfunction "2_2") (pintype "passive"))
      (node (ref "VOUT2") (pin "4") (pinfunction "4_4") (pintype "passive"))
      (node (ref "VOUT2") (pin "6") (pinfunction "6_6") (pintype "passive"))
    )
    (net (code "68") (name "VCC5") (class "Default")
      (node (ref "2.4'/2.8'LCD") (pin "28") (pinfunction "BL_VDD_28") (pintype "passive"))
      (node (ref "C14") (pin "2") (pintype "passive"))
      (node (ref "C23") (pin "1") (pinfunction "VCC_1") (pintype "passive"))
      (node (ref "C25") (pin "2") (pintype "passive"))
      (node (ref "K1") (pin "2") (pinfunction "TAP1_2") (pintype "passive"))
      (node (ref "K1") (pin "5") (pinfunction "TAP2_5") (pintype "passive"))
      (node (ref "U3") (pin "3") (pinfunction "IN_3") (pintype "passive"))
      (node (ref "VOUT3") (pin "2") (pinfunction "2_2") (pintype "passive"))
      (node (ref "VOUT3") (pin "4") (pinfunction "4_4") (pintype "passive"))
      (node (ref "VOUT3") (pin "6") (pinfunction "6_6") (pintype "passive"))
    )
    (net (code "69") (name "unconnected-(2.4'/2.8'LCD-MO-Pad32)") (class "Default")
      (node (ref "2.4'/2.8'LCD") (pin "32") (pinfunction "MO_32") (pintype "passive"))
    )
    (net (code "70") (name "unconnected-(BlueTooth-Pad1)") (class "Default")
      (node (ref "BlueTooth") (pin "1") (pinfunction "1_1") (pintype "passive"))
    )
    (net (code "71") (name "unconnected-(BlueTooth-Pad2)") (class "Default")
      (node (ref "BlueTooth") (pin "2") (pinfunction "2_2") (pintype "passive+no_connect"))
    )
    (net (code "72") (name "unconnected-(BlueTooth-Pad3)") (class "Default")
      (node (ref "BlueTooth") (pin "3") (pinfunction "3_3") (pintype "passive+no_connect"))
    )
    (net (code "73") (name "unconnected-(BlueTooth-Pad6)") (class "Default")
      (node (ref "BlueTooth") (pin "6") (pinfunction "6_6") (pintype "passive"))
    )
    (net (code "74") (name "unconnected-(ECG-Pad1)") (class "Default")
      (node (ref "ECG") (pin "1") (pinfunction "1_1") (pintype "passive"))
    )
    (net (code "75") (name "unconnected-(ECG-Pad3)") (class "Default")
      (node (ref "ECG") (pin "3") (pinfunction "3_3") (pintype "passive"))
    )
    (net (code "76") (name "unconnected-(ECG-Pad4)") (class "Default")
      (node (ref "ECG") (pin "4") (pinfunction "4_4") (pintype "passive"))
    )
    (net (code "77") (name "unconnected-(JTAG-NC-Pad11)") (class "Default")
      (node (ref "JTAG") (pin "11") (pinfunction "NC_11") (pintype "passive"))
    )
    (net (code "78") (name "unconnected-(JTAG-NC-Pad17)") (class "Default")
      (node (ref "JTAG") (pin "17") (pinfunction "NC_17") (pintype "passive"))
    )
    (net (code "79") (name "unconnected-(JTAG-NC-Pad19)") (class "Default")
      (node (ref "JTAG") (pin "19") (pinfunction "NC_19") (pintype "passive"))
    )
    (net (code "80") (name "unconnected-(K1-I{slash}O1-Pad1)") (class "Default")
      (node (ref "K1") (pin "1") (pinfunction "I/O1_1") (pintype "passive"))
    )
    (net (code "81") (name "unconnected-(K1-I{slash}O2-Pad6)") (class "Default")
      (node (ref "K1") (pin "6") (pinfunction "I/O2_6") (pintype "passive"))
    )
    (net (code "82") (name "unconnected-(USB_1-NC-Pad4)") (class "Default")
      (node (ref "USB_1") (pin "4") (pinfunction "NC_4") (pintype "passive"))
    )
  )
)
